# Flash_TF.net
KiCad netlist of a schematic drawn in Altium Designer
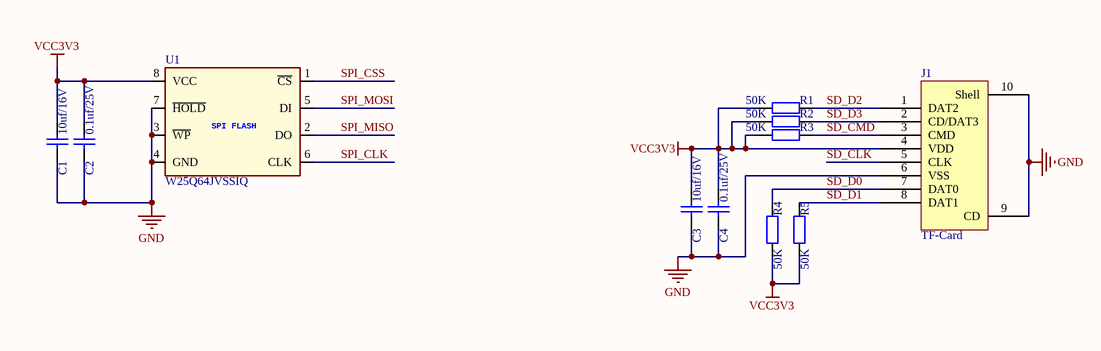
[diagram p0: Flash&TF.SchDoc]

(export (version "E")
  (design (tool "Eeschema 10.0.6"))
  (components
    (comp (ref "C1")
      (value "10uf/16V")
      (footprint "R_C_L:C_0603")
      (description "多层片式陶瓷电容器")
      (libsource (lib "R_C_L") (part "C-0603-10uf/16V-10%"))
    )
    (comp (ref "C2")
      (value "0.1uf/25V")
      (footprint "R_C_L:C_0603")
      (description "多层片式陶瓷电容器")
      (libsource (lib "R_C_L") (part "C-0603-0.1uf/25V-10%"))
    )
    (comp (ref "C3")
      (value "10uf/16V")
      (footprint "R_C_L:C_0603")
      (description "多层片式陶瓷电容器")
      (libsource (lib "R_C_L") (part "C-0603-10uf/16V-10%"))
    )
    (comp (ref "C4")
      (value "0.1uf/25V")
      (footprint "R_C_L:C_0603")
      (description "多层片式陶瓷电容器")
      (libsource (lib "R_C_L") (part "C-0603-0.1uf/25V-10%"))
    )
    (comp (ref "J1")
      (value "TF-Card")
      (footprint "DM3CS-TFCardSlot")
      (description "TF-Card Connector")
      (libsource (lib "Connector") (part "TF-Card"))
    )
    (comp (ref "R1")
      (value "50K")
      (footprint "R_C_L:R_0603")
      (description "通用电阻")
      (libsource (lib "R_C_L") (part "R-0603-50K-1%"))
    )
    (comp (ref "R2")
      (value "50K")
      (footprint "R_C_L:R_0603")
      (description "通用电阻")
      (libsource (lib "R_C_L") (part "R-0603-50K-1%"))
    )
    (comp (ref "R3")
      (value "50K")
      (footprint "R_C_L:R_0603")
      (description "通用电阻")
      (libsource (lib "R_C_L") (part "R-0603-50K-1%"))
    )
    (comp (ref "R4")
      (value "50K")
      (footprint "R_C_L:R_0603")
      (description "通用电阻")
      (libsource (lib "") (part "R-0603-50K-1%_1"))
    )
    (comp (ref "R5")
      (value "50K")
      (footprint "R_C_L:R_0603")
      (description "通用电阻")
      (libsource (lib "") (part "R-0603-50K-1%_1"))
    )
    (comp (ref "U1")
      (value "W25Q64JVSSIQ")
      (footprint "Digital:SOP8")
      (description "SPI FLASH")
      (libsource (lib "Digital") (part "W25Q64"))
    )
  )
  (nets
    (net (code "1") (name "/SD_CLK") (class "Default")
      (node (ref "J1") (pin "5") (pinfunction "CLK_5") (pintype "passive"))
    )
    (net (code "2") (name "/SD_CMD") (class "Default")
      (node (ref "J1") (pin "3") (pinfunction "CMD_3") (pintype "passive"))
      (node (ref "R3") (pin "1") (pinfunction "1_1") (pintype "passive"))
    )
    (net (code "3") (name "/SD_D0") (class "Default")
      (node (ref "J1") (pin "7") (pinfunction "DAT0_7") (pintype "passive"))
      (node (ref "R4") (pin "2") (pinfunction "2_2") (pintype "passive"))
    )
    (net (code "4") (name "/SD_D1") (class "Default")
      (node (ref "J1") (pin "8") (pinfunction "DAT1_8") (pintype "passive"))
      (node (ref "R5") (pin "2") (pinfunction "2_2") (pintype "passive"))
    )
    (net (code "5") (name "/SD_D2") (class "Default")
      (node (ref "J1") (pin "1") (pinfunction "DAT2_1") (pintype "passive"))
      (node (ref "R1") (pin "1") (pinfunction "1_1") (pintype "passive"))
    )
    (net (code "6") (name "/SD_D3") (class "Default")
      (node (ref "J1") (pin "2") (pinfunction "CD/DAT3_2") (pintype "passive"))
      (node (ref "R2") (pin "1") (pinfunction "1_1") (pintype "passive"))
    )
    (net (code "7") (name "/SPI_CLK") (class "Default")
      (node (ref "U1") (pin "6") (pinfunction "CLK_6") (pintype "passive"))
    )
    (net (code "8") (name "/SPI_CSS") (class "Default")
      (node (ref "U1") (pin "1") (pinfunction "~{CS}_1") (pintype "passive"))
    )
    (net (code "9") (name "/SPI_MISO") (class "Default")
      (node (ref "U1") (pin "2") (pinfunction "DO_2") (pintype "passive"))
    )
    (net (code "10") (name "/SPI_MOSI") (class "Default")
      (node (ref "U1") (pin "5") (pinfunction "DI_5") (pintype "passive"))
    )
    (net (code "11") (name "GND") (class "Default")
      (node (ref "C1") (pin "1") (pinfunction "1_1") (pintype "passive"))
      (node (ref "C2") (pin "1") (pinfunction "1_1") (pintype "passive"))
      (node (ref "C3") (pin "1") (pinfunction "1_1") (pintype "passive"))
      (node (ref "C4") (pin "1") (pinfunction "1_1") (pintype "passive"))
      (node (ref "J1") (pin "10") (pinfunction "Shell_10") (pintype "passive"))
      (node (ref "J1") (pin "6") (pinfunction "VSS_6") (pintype "passive"))
      (node (ref "J1") (pin "9") (pinfunction "CD_9") (pintype "passive"))
      (node (ref "U1") (pin "3") (pinfunction "~{WP}_3") (pintype "passive"))
      (node (ref "U1") (pin "4") (pinfunction "GND_4") (pintype "passive"))
      (node (ref "U1") (pin "7") (pinfunction "~{HOLD}_7") (pintype "passive"))
    )
    (net (code "12") (name "VCC3V3") (class "Default")
      (node (ref "C1") (pin "2") (pinfunction "2_2") (pintype "passive"))
      (node (ref "C2") (pin "2") (pinfunction "2_2") (pintype "passive"))
      (node (ref "C3") (pin "2") (pinfunction "2_2") (pintype "passive"))
      (node (ref "C4") (pin "2") (pinfunction "2_2") (pintype "passive"))
      (node (ref "J1") (pin "4") (pinfunction "VDD_4") (pintype "passive"))
      (node (ref "R1") (pin "2") (pinfunction "2_2") (pintype "passive"))
      (node (ref "R2") (pin "2") (pinfunction "2_2") (pintype "passive"))
      (node (ref "R3") (pin "2") (pinfunction "2_2") (pintype "passive"))
      (node (ref "R4") (pin "1") (pinfunction "1_1") (pintype "passive"))
      (node (ref "R5") (pin "1") (pinfunction "1_1") (pintype "passive"))
      (node (ref "U1") (pin "8") (pinfunction "VCC_8") (pintype "passive"))
    )
  )
)
